# Audio-Beamformer_Sensors_V1_0.net
KiCad netlist of a schematic drawn in Altium Designer
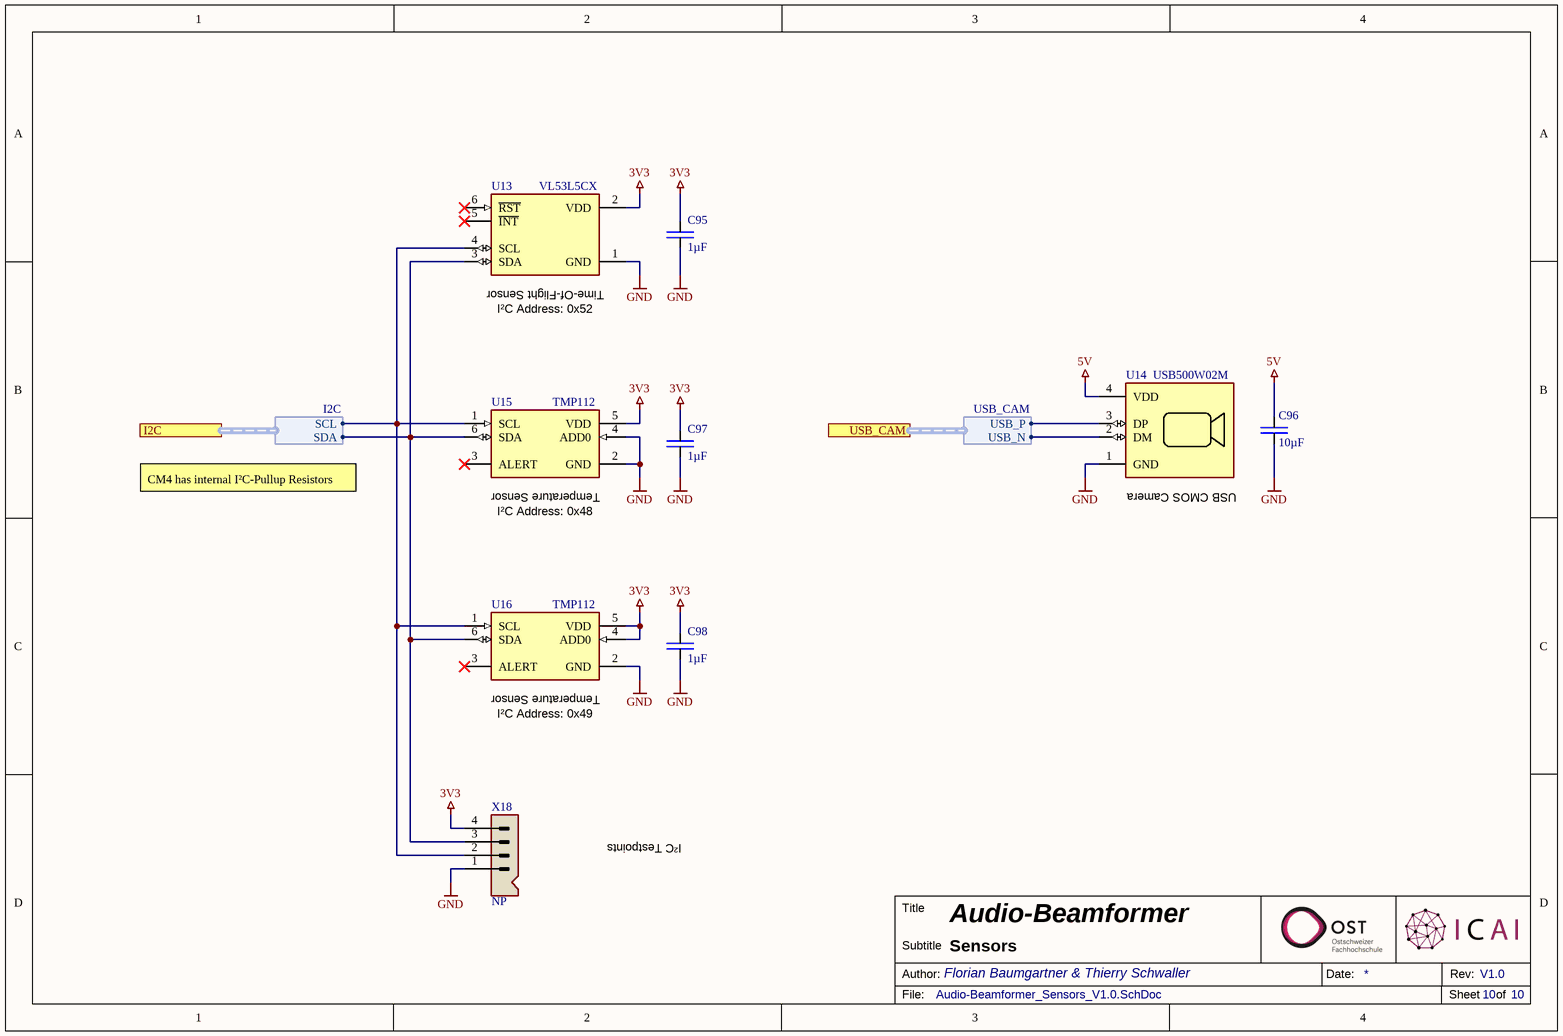
[diagram p0: Audio-Beamformer_Sensors_V1.0.SchDoc]

(export (version "E")
  (design (tool "Eeschema 10.0.6"))
  (components
    (comp (ref "C95")
      (value "1µF")
      (footprint "SMD Keramikkondensator 0603")
      (description "CAP-MK")
      (libsource (lib "AudioAmp") (part "C-CAPACITOR"))
    )
    (comp (ref "C96")
      (value "10µF")
      (footprint "SMD Keramikkondensator 1206")
      (description "CAP-MK")
      (libsource (lib "AudioAmp") (part "C-CAPACITOR"))
    )
    (comp (ref "C97")
      (value "1µF")
      (footprint "SMD Keramikkondensator 0603")
      (description "CAP-MK")
      (libsource (lib "AudioAmp") (part "C-CAPACITOR"))
    )
    (comp (ref "C98")
      (value "1µF")
      (footprint "SMD Keramikkondensator 0603")
      (description "CAP-MK")
      (libsource (lib "AudioAmp") (part "C-CAPACITOR"))
    )
    (comp (ref "U13")
      (value "VL53L5CX")
      (footprint "THT ToF-Sensor (VL53L5CX)")
      (description "Time-of-Flight 8x8 Multizone Sensor")
      (libsource (lib "Audio-Beamformer") (part "U-VL53L5CX"))
    )
    (comp (ref "U14")
      (value "USB500W02M")
      (footprint "THT Camera (USB500W02M)")
      (description "USB 5.0 Megapixel CMOS Camera Module")
      (libsource (lib "Audio-Beamformer") (part "U-USB500W02M"))
    )
    (comp (ref "U15")
      (value "TMP112")
      (footprint "SMD IC SOT-563")
      (description "High-Accuracy, Low-Power, Digital Temperature Sensor")
      (libsource (lib "Audio-Beamformer") (part "U-TMP112AIDRLR"))
    )
    (comp (ref "U16")
      (value "TMP112")
      (footprint "SMD IC SOT-563")
      (description "High-Accuracy, Low-Power, Digital Temperature Sensor")
      (libsource (lib "Audio-Beamformer") (part "U-TMP112AIDRLR"))
    )
    (comp (ref "X18")
      (value "NP")
      (footprint "THT Pin-Header 4x1 (NP)")
      (libsource (lib "Audio-Beamformer") (part "X-Stiftleiste (4-Fach)"))
    )
  )
  (nets
    (net (code "3") (name "/SCL") (class "Default")
      (node (ref "U13") (pin "4") (pinfunction "SCL_4") (pintype "bidirectional"))
      (node (ref "U15") (pin "1") (pinfunction "SCL_1") (pintype "input"))
      (node (ref "U16") (pin "1") (pinfunction "SCL_1") (pintype "input"))
      (node (ref "X18") (pin "2") (pinfunction "2_2") (pintype "passive"))
    )
    (net (code "4") (name "/SDA") (class "Default")
      (node (ref "U13") (pin "3") (pinfunction "SDA_3") (pintype "bidirectional"))
      (node (ref "U15") (pin "6") (pinfunction "SDA_6") (pintype "bidirectional"))
      (node (ref "U16") (pin "6") (pinfunction "SDA_6") (pintype "bidirectional"))
      (node (ref "X18") (pin "3") (pinfunction "3_3") (pintype "passive"))
    )
    (net (code "5") (name "/USB_N") (class "Default")
      (node (ref "U14") (pin "2") (pinfunction "DM_2") (pintype "bidirectional"))
    )
    (net (code "6") (name "/USB_P") (class "Default")
      (node (ref "U14") (pin "3") (pinfunction "DP_3") (pintype "bidirectional"))
    )
    (net (code "9") (name "3V3") (class "Default")
      (node (ref "C95") (pin "2") (pinfunction "2_2") (pintype "passive"))
      (node (ref "C97") (pin "2") (pinfunction "2_2") (pintype "passive"))
      (node (ref "C98") (pin "2") (pinfunction "2_2") (pintype "passive"))
      (node (ref "U13") (pin "2") (pinfunction "VDD_2") (pintype "power_in"))
      (node (ref "U15") (pin "5") (pinfunction "VDD_5") (pintype "power_in"))
      (node (ref "U16") (pin "4") (pinfunction "ADD0_4") (pintype "input"))
      (node (ref "U16") (pin "5") (pinfunction "VDD_5") (pintype "power_in"))
      (node (ref "X18") (pin "4") (pinfunction "4_4") (pintype "passive"))
    )
    (net (code "10") (name "5V") (class "Default")
      (node (ref "C96") (pin "2") (pinfunction "2_2") (pintype "passive"))
      (node (ref "U14") (pin "4") (pinfunction "VDD_4") (pintype "power_in"))
    )
    (net (code "11") (name "GND") (class "Default")
      (node (ref "C95") (pin "1") (pinfunction "1_1") (pintype "passive"))
      (node (ref "C96") (pin "1") (pinfunction "1_1") (pintype "passive"))
      (node (ref "C97") (pin "1") (pinfunction "1_1") (pintype "passive"))
      (node (ref "C98") (pin "1") (pinfunction "1_1") (pintype "passive"))
      (node (ref "U13") (pin "1") (pinfunction "GND_1") (pintype "power_in"))
      (node (ref "U14") (pin "1") (pinfunction "GND_1") (pintype "power_in"))
      (node (ref "U15") (pin "2") (pinfunction "GND_2") (pintype "power_in"))
      (node (ref "U15") (pin "4") (pinfunction "ADD0_4") (pintype "input"))
      (node (ref "U16") (pin "2") (pinfunction "GND_2") (pintype "power_in"))
      (node (ref "X18") (pin "1") (pinfunction "1_1") (pintype "passive"))
    )
    (net (code "12") (name "unconnected-(U13-~{INT}-Pad5)") (class "Default")
      (node (ref "U13") (pin "5") (pinfunction "~{INT}_5") (pintype "open_collector+no_connect"))
    )
    (net (code "13") (name "unconnected-(U13-~{RST}-Pad6)") (class "Default")
      (node (ref "U13") (pin "6") (pinfunction "~{RST}_6") (pintype "input+no_connect"))
    )
    (net (code "14") (name "unconnected-(U15-ALERT-Pad3)") (class "Default")
      (node (ref "U15") (pin "3") (pinfunction "ALERT_3") (pintype "open_collector+no_connect"))
    )
    (net (code "15") (name "unconnected-(U16-ALERT-Pad3)") (class "Default")
      (node (ref "U16") (pin "3") (pinfunction "ALERT_3") (pintype "open_collector+no_connect"))
    )
  )
)
